# 05_ElectronicScales.net
KiCad netlist of a schematic drawn in Altium Designer
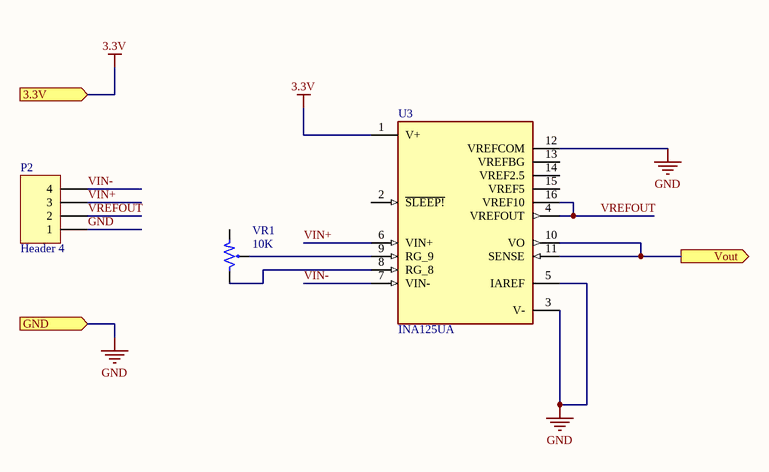
[diagram p0: 05_ElectronicScales.SchDoc]

(export (version "E")
  (design (tool "Eeschema 10.0.6"))
  (components
    (comp (ref "P2")
      (value "Header 4")
      (footprint "HDR1X4")
      (description "Header, 4-Pin")
      (fields (field (name "PUBLISHER") "Altium Limited"))
      (libsource (lib "My Library") (part "Header 4"))
    )
    (comp (ref "U3")
      (value "INA125UA")
      (footprint "SOIC127P600X175-16N")
      (description "Instrumentation Amplifier with Precision Voltage Reference 16-SOIC")
      (libsource (lib "INA125UA") (part "INA125UA"))
    )
    (comp (ref "VR1")
      (value "10K")
      (footprint "VR")
      (description "Var Resistor")
      (libsource (lib "My Library") (part "VR1"))
    )
  )
  (nets
    (net (code "1") (name "/VIN+") (class "Default")
      (node (ref "P2") (pin "3") (pinfunction "3_3") (pintype "passive"))
      (node (ref "U3") (pin "6") (pinfunction "VIN+_6") (pintype "input"))
    )
    (net (code "2") (name "/VIN-") (class "Default")
      (node (ref "P2") (pin "4") (pinfunction "4_4") (pintype "passive"))
      (node (ref "U3") (pin "7") (pinfunction "VIN-_7") (pintype "input"))
    )
    (net (code "3") (name "/VREFOUT") (class "Default")
      (node (ref "P2") (pin "2") (pinfunction "2_2") (pintype "passive"))
      (node (ref "U3") (pin "16") (pinfunction "VREF10_16") (pintype "passive"))
      (node (ref "U3") (pin "4") (pinfunction "VREFOUT_4") (pintype "output"))
    )
    (net (code "4") (name "/Vout") (class "Default")
      (node (ref "U3") (pin "10") (pinfunction "VO_10") (pintype "output"))
      (node (ref "U3") (pin "11") (pinfunction "SENSE_11") (pintype "input"))
    )
    (net (code "5") (name "3.3V") (class "Default")
      (node (ref "U3") (pin "1") (pinfunction "V+_1") (pintype "power_in"))
    )
    (net (code "6") (name "GND") (class "Default")
      (node (ref "P2") (pin "1") (pinfunction "1_1") (pintype "passive"))
      (node (ref "U3") (pin "12") (pinfunction "VREFCOM_12") (pintype "passive"))
      (node (ref "U3") (pin "3") (pinfunction "V-_3") (pintype "power_in"))
      (node (ref "U3") (pin "5") (pinfunction "IAREF_5") (pintype "passive"))
    )
    (net (code "7") (name "Net-(U3-RG_8)") (class "Default")
      (node (ref "U3") (pin "8") (pinfunction "RG_8_8") (pintype "input"))
      (node (ref "VR1") (pin "3") (pinfunction "3_3") (pintype "passive"))
    )
    (net (code "8") (name "Net-(U3-RG_9)") (class "Default")
      (node (ref "U3") (pin "9") (pinfunction "RG_9_9") (pintype "input"))
      (node (ref "VR1") (pin "2") (pinfunction "2_2") (pintype "passive"))
    )
    (net (code "9") (name "unconnected-(U3-VREF2.5-Pad14)") (class "Default")
      (node (ref "U3") (pin "14") (pinfunction "VREF2.5_14") (pintype "passive"))
    )
    (net (code "10") (name "unconnected-(U3-VREF5-Pad15)") (class "Default")
      (node (ref "U3") (pin "15") (pinfunction "VREF5_15") (pintype "passive"))
    )
    (net (code "11") (name "unconnected-(U3-VREFBG-Pad13)") (class "Default")
      (node (ref "U3") (pin "13") (pinfunction "VREFBG_13") (pintype "passive"))
    )
    (net (code "12") (name "unconnected-(U3-~{SLEEP!}-Pad2)") (class "Default")
      (node (ref "U3") (pin "2") (pinfunction "~{SLEEP!}_2") (pintype "input"))
    )
    (net (code "13") (name "unconnected-(VR1-Pad1)") (class "Default")
      (node (ref "VR1") (pin "1") (pinfunction "1_1") (pintype "passive"))
    )
  )
)
